# pfeffer_sub_curcuit_2.net
KiCad netlist of a schematic drawn in EAGLE
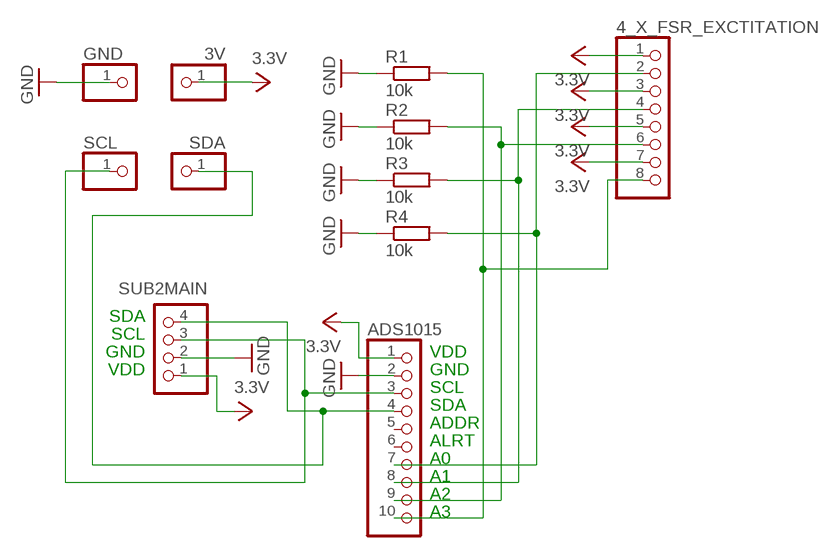
[diagram p0: schematic, sheet 1]

(export (version "E")
  (design (tool "Eeschema 10.0.6"))
  (components
    (comp (ref "3V")
      (value "PINHD-1X1")
      (footprint "eagle-import:1X01")
      (libsource (lib "eagle-import") (part "PINHD-1X1"))
    )
    (comp (ref "4_X_FSR_EXCTITATION")
      (value "PINHD-1X8")
      (footprint "eagle-import:1X08")
      (libsource (lib "eagle-import") (part "PINHD-1X8"))
    )
    (comp (ref "ADS1015")
      (value "PINHD-1X10")
      (footprint "eagle-import:1X10")
      (libsource (lib "eagle-import") (part "PINHD-1X10"))
    )
    (comp (ref "GND")
      (value "PINHD-1X1")
      (footprint "eagle-import:1X01")
      (libsource (lib "eagle-import") (part "PINHD-1X1"))
    )
    (comp (ref "R1")
      (value "10k")
      (footprint "eagle-import:0204_7")
      (libsource (lib "eagle-import") (part "R-EU_0204/7"))
    )
    (comp (ref "R2")
      (value "10k")
      (footprint "eagle-import:0204_7")
      (libsource (lib "eagle-import") (part "R-EU_0204/7"))
    )
    (comp (ref "R3")
      (value "10k")
      (footprint "eagle-import:0204_7")
      (libsource (lib "eagle-import") (part "R-EU_0204/7"))
    )
    (comp (ref "R4")
      (value "10k")
      (footprint "eagle-import:0204_7")
      (libsource (lib "eagle-import") (part "R-EU_0204/7"))
    )
    (comp (ref "SCL")
      (value "PINHD-1X1")
      (footprint "eagle-import:1X01")
      (libsource (lib "eagle-import") (part "PINHD-1X1"))
    )
    (comp (ref "SDA")
      (value "PINHD-1X1")
      (footprint "eagle-import:1X01")
      (libsource (lib "eagle-import") (part "PINHD-1X1"))
    )
    (comp (ref "SUB2MAIN")
      (value "PINHD-1X4")
      (footprint "eagle-import:1X04")
      (libsource (lib "eagle-import") (part "PINHD-1X4"))
    )
  )
  (nets
    (net (code "1") (name "3.3V") (class "Default")
      (node (ref "3V") (pin "1") (pinfunction "1_1") (pintype "passive"))
      (node (ref "4_X_FSR_EXCTITATION") (pin "1") (pinfunction "1_1") (pintype "passive"))
      (node (ref "4_X_FSR_EXCTITATION") (pin "3") (pinfunction "3_3") (pintype "passive"))
      (node (ref "4_X_FSR_EXCTITATION") (pin "5") (pinfunction "5_5") (pintype "passive"))
      (node (ref "4_X_FSR_EXCTITATION") (pin "7") (pinfunction "7_7") (pintype "passive"))
      (node (ref "ADS1015") (pin "1") (pinfunction "1_1") (pintype "passive"))
      (node (ref "SUB2MAIN") (pin "1") (pinfunction "1_1") (pintype "passive"))
    )
    (net (code "2") (name "GND") (class "Default")
      (node (ref "ADS1015") (pin "2") (pinfunction "2_2") (pintype "passive"))
      (node (ref "GND") (pin "1") (pinfunction "1_1") (pintype "passive"))
      (node (ref "R1") (pin "1") (pinfunction "1_1") (pintype "passive"))
      (node (ref "R2") (pin "1") (pinfunction "1_1") (pintype "passive"))
      (node (ref "R3") (pin "1") (pinfunction "1_1") (pintype "passive"))
      (node (ref "R4") (pin "1") (pinfunction "1_1") (pintype "passive"))
      (node (ref "SUB2MAIN") (pin "2") (pinfunction "2_2") (pintype "passive"))
    )
    (net (code "3") (name "Net-(4_X_FSR_EXCTITATION-Pad2)") (class "Default")
      (node (ref "4_X_FSR_EXCTITATION") (pin "2") (pinfunction "2_2") (pintype "passive"))
      (node (ref "ADS1015") (pin "7") (pinfunction "7_7") (pintype "passive"))
      (node (ref "R4") (pin "2") (pinfunction "2_2") (pintype "passive"))
    )
    (net (code "4") (name "Net-(4_X_FSR_EXCTITATION-Pad4)") (class "Default")
      (node (ref "4_X_FSR_EXCTITATION") (pin "4") (pinfunction "4_4") (pintype "passive"))
      (node (ref "ADS1015") (pin "8") (pinfunction "8_8") (pintype "passive"))
      (node (ref "R3") (pin "2") (pinfunction "2_2") (pintype "passive"))
    )
    (net (code "5") (name "Net-(4_X_FSR_EXCTITATION-Pad6)") (class "Default")
      (node (ref "4_X_FSR_EXCTITATION") (pin "6") (pinfunction "6_6") (pintype "passive"))
      (node (ref "ADS1015") (pin "9") (pinfunction "9_9") (pintype "passive"))
      (node (ref "R2") (pin "2") (pinfunction "2_2") (pintype "passive"))
    )
    (net (code "6") (name "Net-(4_X_FSR_EXCTITATION-Pad8)") (class "Default")
      (node (ref "4_X_FSR_EXCTITATION") (pin "8") (pinfunction "8_8") (pintype "passive"))
      (node (ref "ADS1015") (pin "10") (pinfunction "10_10") (pintype "passive"))
      (node (ref "R1") (pin "2") (pinfunction "2_2") (pintype "passive"))
    )
    (net (code "7") (name "Net-(ADS1015-Pad3)") (class "Default")
      (node (ref "ADS1015") (pin "3") (pinfunction "3_3") (pintype "passive"))
      (node (ref "SCL") (pin "1") (pinfunction "1_1") (pintype "passive"))
      (node (ref "SUB2MAIN") (pin "3") (pinfunction "3_3") (pintype "passive"))
    )
    (net (code "8") (name "Net-(ADS1015-Pad4)") (class "Default")
      (node (ref "ADS1015") (pin "4") (pinfunction "4_4") (pintype "passive"))
      (node (ref "SDA") (pin "1") (pinfunction "1_1") (pintype "passive"))
      (node (ref "SUB2MAIN") (pin "4") (pinfunction "4_4") (pintype "passive"))
    )
    (net (code "9") (name "unconnected-(ADS1015-Pad5)") (class "Default")
      (node (ref "ADS1015") (pin "5") (pinfunction "5_5") (pintype "passive"))
    )
    (net (code "10") (name "unconnected-(ADS1015-Pad6)") (class "Default")
      (node (ref "ADS1015") (pin "6") (pinfunction "6_6") (pintype "passive"))
    )
  )
)
